# untitled.net
KiCad netlist of a schematic drawn in EAGLE
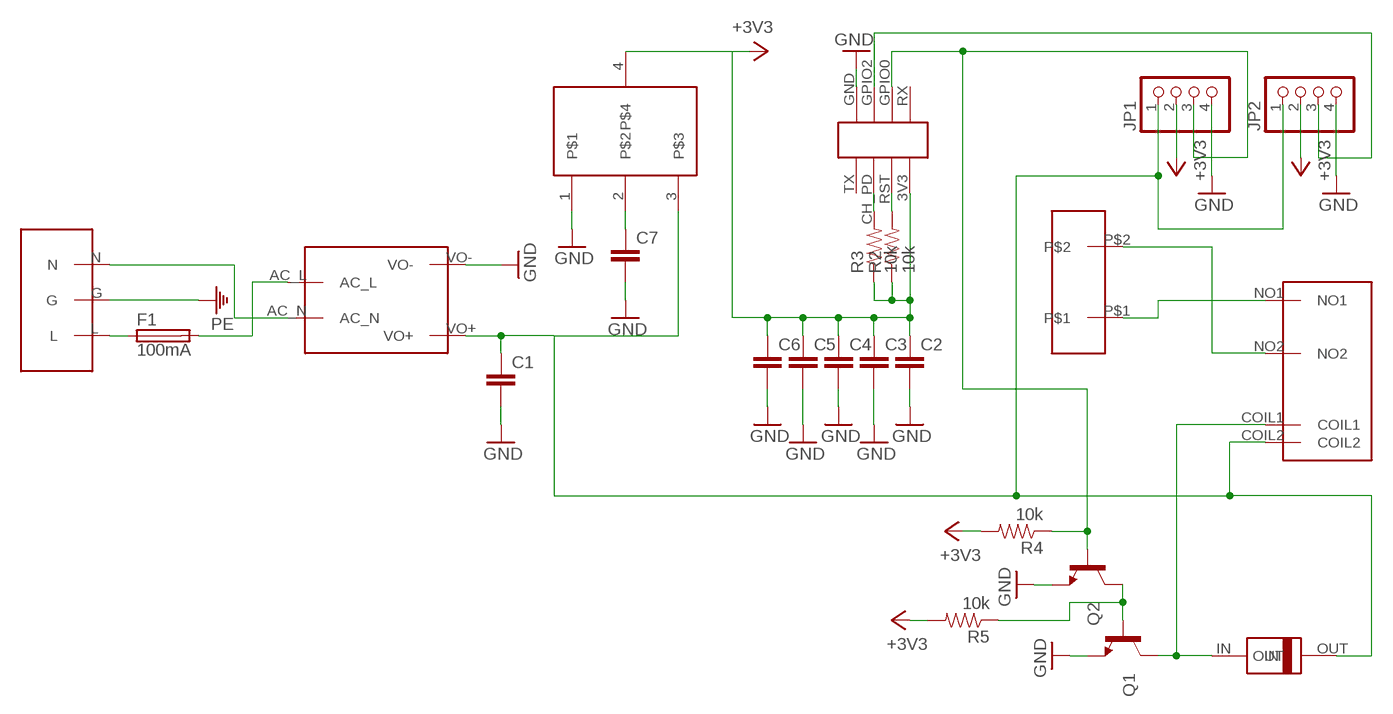
[diagram p0: schematic, sheet 1]

(export (version "E")
  (design (tool "Eeschema 10.0.6"))
  (components
    (comp (ref "C1")
      (value "CAP0805")
      (footprint "eagle-import:0805")
      (libsource (lib "eagle-import") (part "CAP0805"))
    )
    (comp (ref "C2")
      (value "CAP0805")
      (footprint "eagle-import:0805")
      (libsource (lib "eagle-import") (part "CAP0805"))
    )
    (comp (ref "C3")
      (value "CAP0805")
      (footprint "eagle-import:0805")
      (libsource (lib "eagle-import") (part "CAP0805"))
    )
    (comp (ref "C4")
      (value "CAP0805")
      (footprint "eagle-import:0805")
      (libsource (lib "eagle-import") (part "CAP0805"))
    )
    (comp (ref "C5")
      (value "CAP0805")
      (footprint "eagle-import:0805")
      (libsource (lib "eagle-import") (part "CAP0805"))
    )
    (comp (ref "C6")
      (value "CAP0805")
      (footprint "eagle-import:0805")
      (libsource (lib "eagle-import") (part "CAP0805"))
    )
    (comp (ref "C7")
      (value "CAP0805")
      (footprint "eagle-import:0805")
      (libsource (lib "eagle-import") (part "CAP0805"))
    )
    (comp (ref "DIODE1")
      (value "DIODE_1N4148WQ-7-F")
      (footprint "eagle-import:DIODE_1N4148WQ-7-F")
      (libsource (lib "eagle-import") (part "DIODE_1N4148WQ-7-F"))
    )
    (comp (ref "F1")
      (value "100mA")
      (footprint "eagle-import:SH22,5A")
      (fields (field (name "MPN") "0031.7701.11"))
      (libsource (lib "eagle-import") (part "SH22,5A"))
    )
    (comp (ref "JP1")
      (value "PINHD-1X4")
      (footprint "eagle-import:1X04")
      (libsource (lib "eagle-import") (part "PINHD-1X4"))
    )
    (comp (ref "JP2")
      (value "PINHD-1X4")
      (footprint "eagle-import:1X04")
      (libsource (lib "eagle-import") (part "PINHD-1X4"))
    )
    (comp (ref "Q1")
      (value "TRANSISTOR_NPNSOT23")
      (footprint "eagle-import:SOT23")
      (libsource (lib "eagle-import") (part "TRANSISTOR_NPNSOT23"))
    )
    (comp (ref "Q2")
      (value "TRANSISTOR_NPNSOT23")
      (footprint "eagle-import:SOT23")
      (libsource (lib "eagle-import") (part "TRANSISTOR_NPNSOT23"))
    )
    (comp (ref "R2")
      (value "10k")
      (footprint "eagle-import:0603-RES")
      (libsource (lib "eagle-import") (part "220-5%"))
    )
    (comp (ref "R3")
      (value "10k")
      (footprint "eagle-import:0603-RES")
      (libsource (lib "eagle-import") (part "220-5%"))
    )
    (comp (ref "R4")
      (value "10k")
      (footprint "eagle-import:0603-RES")
      (libsource (lib "eagle-import") (part "220-5%"))
    )
    (comp (ref "R5")
      (value "10k")
      (footprint "eagle-import:0603-RES")
      (libsource (lib "eagle-import") (part "220-5%"))
    )
    (comp (ref "U$1")
      (value "MAINS_CONVERTERS")
      (footprint "eagle-import:HLK-PM01")
      (libsource (lib "eagle-import") (part "MAINS_CONVERTERS"))
    )
    (comp (ref "U$2")
      (value "SCREWTERMINALS_5MM")
      (footprint "eagle-import:3PIN_LNG")
      (libsource (lib "eagle-import") (part "SCREWTERMINALS_5MM"))
    )
    (comp (ref "U$4")
      (value "VREG")
      (footprint "eagle-import:SOT223")
      (libsource (lib "eagle-import") (part "VREG"))
    )
    (comp (ref "U$5")
      (value "SCREWTERMINALS_5MM_2")
      (footprint "eagle-import:TERMINAL_2X")
      (libsource (lib "eagle-import") (part "SCREWTERMINALS_5MM_2"))
    )
    (comp (ref "U$6")
      (value "OMRON_G6M-1A")
      (footprint "eagle-import:OMRON_G6M-1A")
      (libsource (lib "eagle-import") (part "OMRON_G6M-1A"))
    )
    (comp (ref "U$7")
      (value "ESP8266-01")
      (footprint "eagle-import:ESP8266-01")
      (libsource (lib "eagle-import") (part "ESP8266-01"))
    )
  )
  (nets
    (net (code "1") (name "+3V3") (class "Default")
      (node (ref "C2") (pin "1") (pinfunction "1_1") (pintype "passive"))
      (node (ref "C3") (pin "1") (pinfunction "1_1") (pintype "passive"))
      (node (ref "C4") (pin "1") (pinfunction "1_1") (pintype "passive"))
      (node (ref "C5") (pin "1") (pinfunction "1_1") (pintype "passive"))
      (node (ref "C6") (pin "1") (pinfunction "1_1") (pintype "passive"))
      (node (ref "JP1") (pin "2") (pinfunction "2_2") (pintype "passive"))
      (node (ref "JP2") (pin "2") (pinfunction "2_2") (pintype "passive"))
      (node (ref "R2") (pin "1") (pinfunction "1_1") (pintype "passive"))
      (node (ref "R3") (pin "1") (pinfunction "1_1") (pintype "passive"))
      (node (ref "R4") (pin "2") (pinfunction "2_2") (pintype "passive"))
      (node (ref "R5") (pin "2") (pinfunction "2_2") (pintype "passive"))
      (node (ref "U$4") (pin "4") (pinfunction "P$4_4") (pintype "bidirectional"))
      (node (ref "U$7") (pin "3V3") (pinfunction "3V3_3V3") (pintype "bidirectional"))
    )
    (net (code "2") (name "GND") (class "Default")
      (node (ref "C1") (pin "2") (pinfunction "2_2") (pintype "passive"))
      (node (ref "C2") (pin "2") (pinfunction "2_2") (pintype "passive"))
      (node (ref "C3") (pin "2") (pinfunction "2_2") (pintype "passive"))
      (node (ref "C4") (pin "2") (pinfunction "2_2") (pintype "passive"))
      (node (ref "C5") (pin "2") (pinfunction "2_2") (pintype "passive"))
      (node (ref "C6") (pin "2") (pinfunction "2_2") (pintype "passive"))
      (node (ref "C7") (pin "2") (pinfunction "2_2") (pintype "passive"))
      (node (ref "JP1") (pin "4") (pinfunction "4_4") (pintype "passive"))
      (node (ref "JP2") (pin "4") (pinfunction "4_4") (pintype "passive"))
      (node (ref "Q1") (pin "2") (pinfunction "E_2") (pintype "passive"))
      (node (ref "Q2") (pin "2") (pinfunction "E_2") (pintype "passive"))
      (node (ref "U$1") (pin "VO-") (pinfunction "VO-_VO-") (pintype "output"))
      (node (ref "U$4") (pin "1") (pinfunction "P$1_1") (pintype "bidirectional"))
      (node (ref "U$7") (pin "GND") (pinfunction "GND_GND") (pintype "bidirectional"))
    )
    (net (code "3") (name "Net-(F1-Pad1)") (class "Default")
      (node (ref "F1") (pin "1") (pinfunction "1_1") (pintype "passive"))
      (node (ref "U$2") (pin "L") (pinfunction "L_L") (pintype "bidirectional"))
    )
    (net (code "4") (name "Net-(F1-Pad2)") (class "Default")
      (node (ref "F1") (pin "2") (pinfunction "2_2") (pintype "passive"))
      (node (ref "U$1") (pin "AC_L") (pinfunction "AC_L_AC_L") (pintype "input"))
    )
    (net (code "5") (name "Net-(JP2-Pad3)") (class "Default")
      (node (ref "JP2") (pin "3") (pinfunction "3_3") (pintype "passive"))
      (node (ref "U$7") (pin "GPIO2") (pinfunction "GPIO2_GPIO2") (pintype "bidirectional"))
    )
    (net (code "6") (name "Net-(Q1-B)") (class "Default")
      (node (ref "Q1") (pin "1") (pinfunction "B_1") (pintype "passive"))
      (node (ref "Q2") (pin "3") (pinfunction "C_3") (pintype "passive"))
      (node (ref "R5") (pin "1") (pinfunction "1_1") (pintype "passive"))
    )
    (net (code "7") (name "Net-(Q1-C)") (class "Default")
      (node (ref "DIODE1") (pin "IN") (pinfunction "IN_IN") (pintype "input"))
      (node (ref "Q1") (pin "3") (pinfunction "C_3") (pintype "passive"))
      (node (ref "U$6") (pin "COIL1") (pinfunction "COIL1_COIL1") (pintype "bidirectional"))
    )
    (net (code "8") (name "Net-(Q2-B)") (class "Default")
      (node (ref "JP1") (pin "3") (pinfunction "3_3") (pintype "passive"))
      (node (ref "Q2") (pin "1") (pinfunction "B_1") (pintype "passive"))
      (node (ref "R4") (pin "1") (pinfunction "1_1") (pintype "passive"))
      (node (ref "U$7") (pin "GPIO0") (pinfunction "GPIO0_GPIO0") (pintype "bidirectional"))
    )
    (net (code "9") (name "Net-(R2-Pad2)") (class "Default")
      (node (ref "R2") (pin "2") (pinfunction "2_2") (pintype "passive"))
      (node (ref "U$7") (pin "RST") (pinfunction "RST_RST") (pintype "bidirectional"))
    )
    (net (code "10") (name "Net-(R3-Pad2)") (class "Default")
      (node (ref "R3") (pin "2") (pinfunction "2_2") (pintype "passive"))
      (node (ref "U$7") (pin "CH_PD") (pinfunction "CH_PD_CH_PD") (pintype "bidirectional"))
    )
    (net (code "11") (name "Net-(U$1-PadAC_N)") (class "Default")
      (node (ref "U$1") (pin "AC_N") (pinfunction "AC_N_AC_N") (pintype "input"))
      (node (ref "U$2") (pin "N") (pinfunction "N_N") (pintype "bidirectional"))
    )
    (net (code "12") (name "Net-(U$4-P$2)") (class "Default")
      (node (ref "C7") (pin "1") (pinfunction "1_1") (pintype "passive"))
      (node (ref "U$4") (pin "2") (pinfunction "P$2_2") (pintype "bidirectional"))
    )
    (net (code "13") (name "Net-(U$4-P$3)") (class "Default")
      (node (ref "C1") (pin "1") (pinfunction "1_1") (pintype "passive"))
      (node (ref "DIODE1") (pin "OUT") (pinfunction "OUT_OUT") (pintype "output"))
      (node (ref "JP1") (pin "1") (pinfunction "1_1") (pintype "passive"))
      (node (ref "JP2") (pin "1") (pinfunction "1_1") (pintype "passive"))
      (node (ref "U$1") (pin "VO+") (pinfunction "VO+_VO+") (pintype "output"))
      (node (ref "U$4") (pin "3") (pinfunction "P$3_3") (pintype "bidirectional"))
      (node (ref "U$6") (pin "COIL2") (pinfunction "COIL2_COIL2") (pintype "bidirectional"))
    )
    (net (code "14") (name "Net-(U$5-PadP$1)") (class "Default")
      (node (ref "U$5") (pin "P$1") (pinfunction "P$1_P$1") (pintype "bidirectional"))
      (node (ref "U$6") (pin "NO1") (pinfunction "NO1_NO1") (pintype "bidirectional"))
    )
    (net (code "15") (name "Net-(U$5-PadP$2)") (class "Default")
      (node (ref "U$5") (pin "P$2") (pinfunction "P$2_P$2") (pintype "bidirectional"))
      (node (ref "U$6") (pin "NO2") (pinfunction "NO2_NO2") (pintype "bidirectional"))
    )
    (net (code "16") (name "PE") (class "Default")
      (node (ref "U$2") (pin "G") (pinfunction "G_G") (pintype "bidirectional"))
    )
    (net (code "17") (name "unconnected-(U$7-PadRX)") (class "Default")
      (node (ref "U$7") (pin "RX") (pinfunction "RX_RX") (pintype "bidirectional"))
    )
    (net (code "18") (name "unconnected-(U$7-PadTX)") (class "Default")
      (node (ref "U$7") (pin "TX") (pinfunction "TX_TX") (pintype "bidirectional"))
    )
  )
)
